# Schematic.net
KiCad netlist of a schematic drawn in Altium Designer
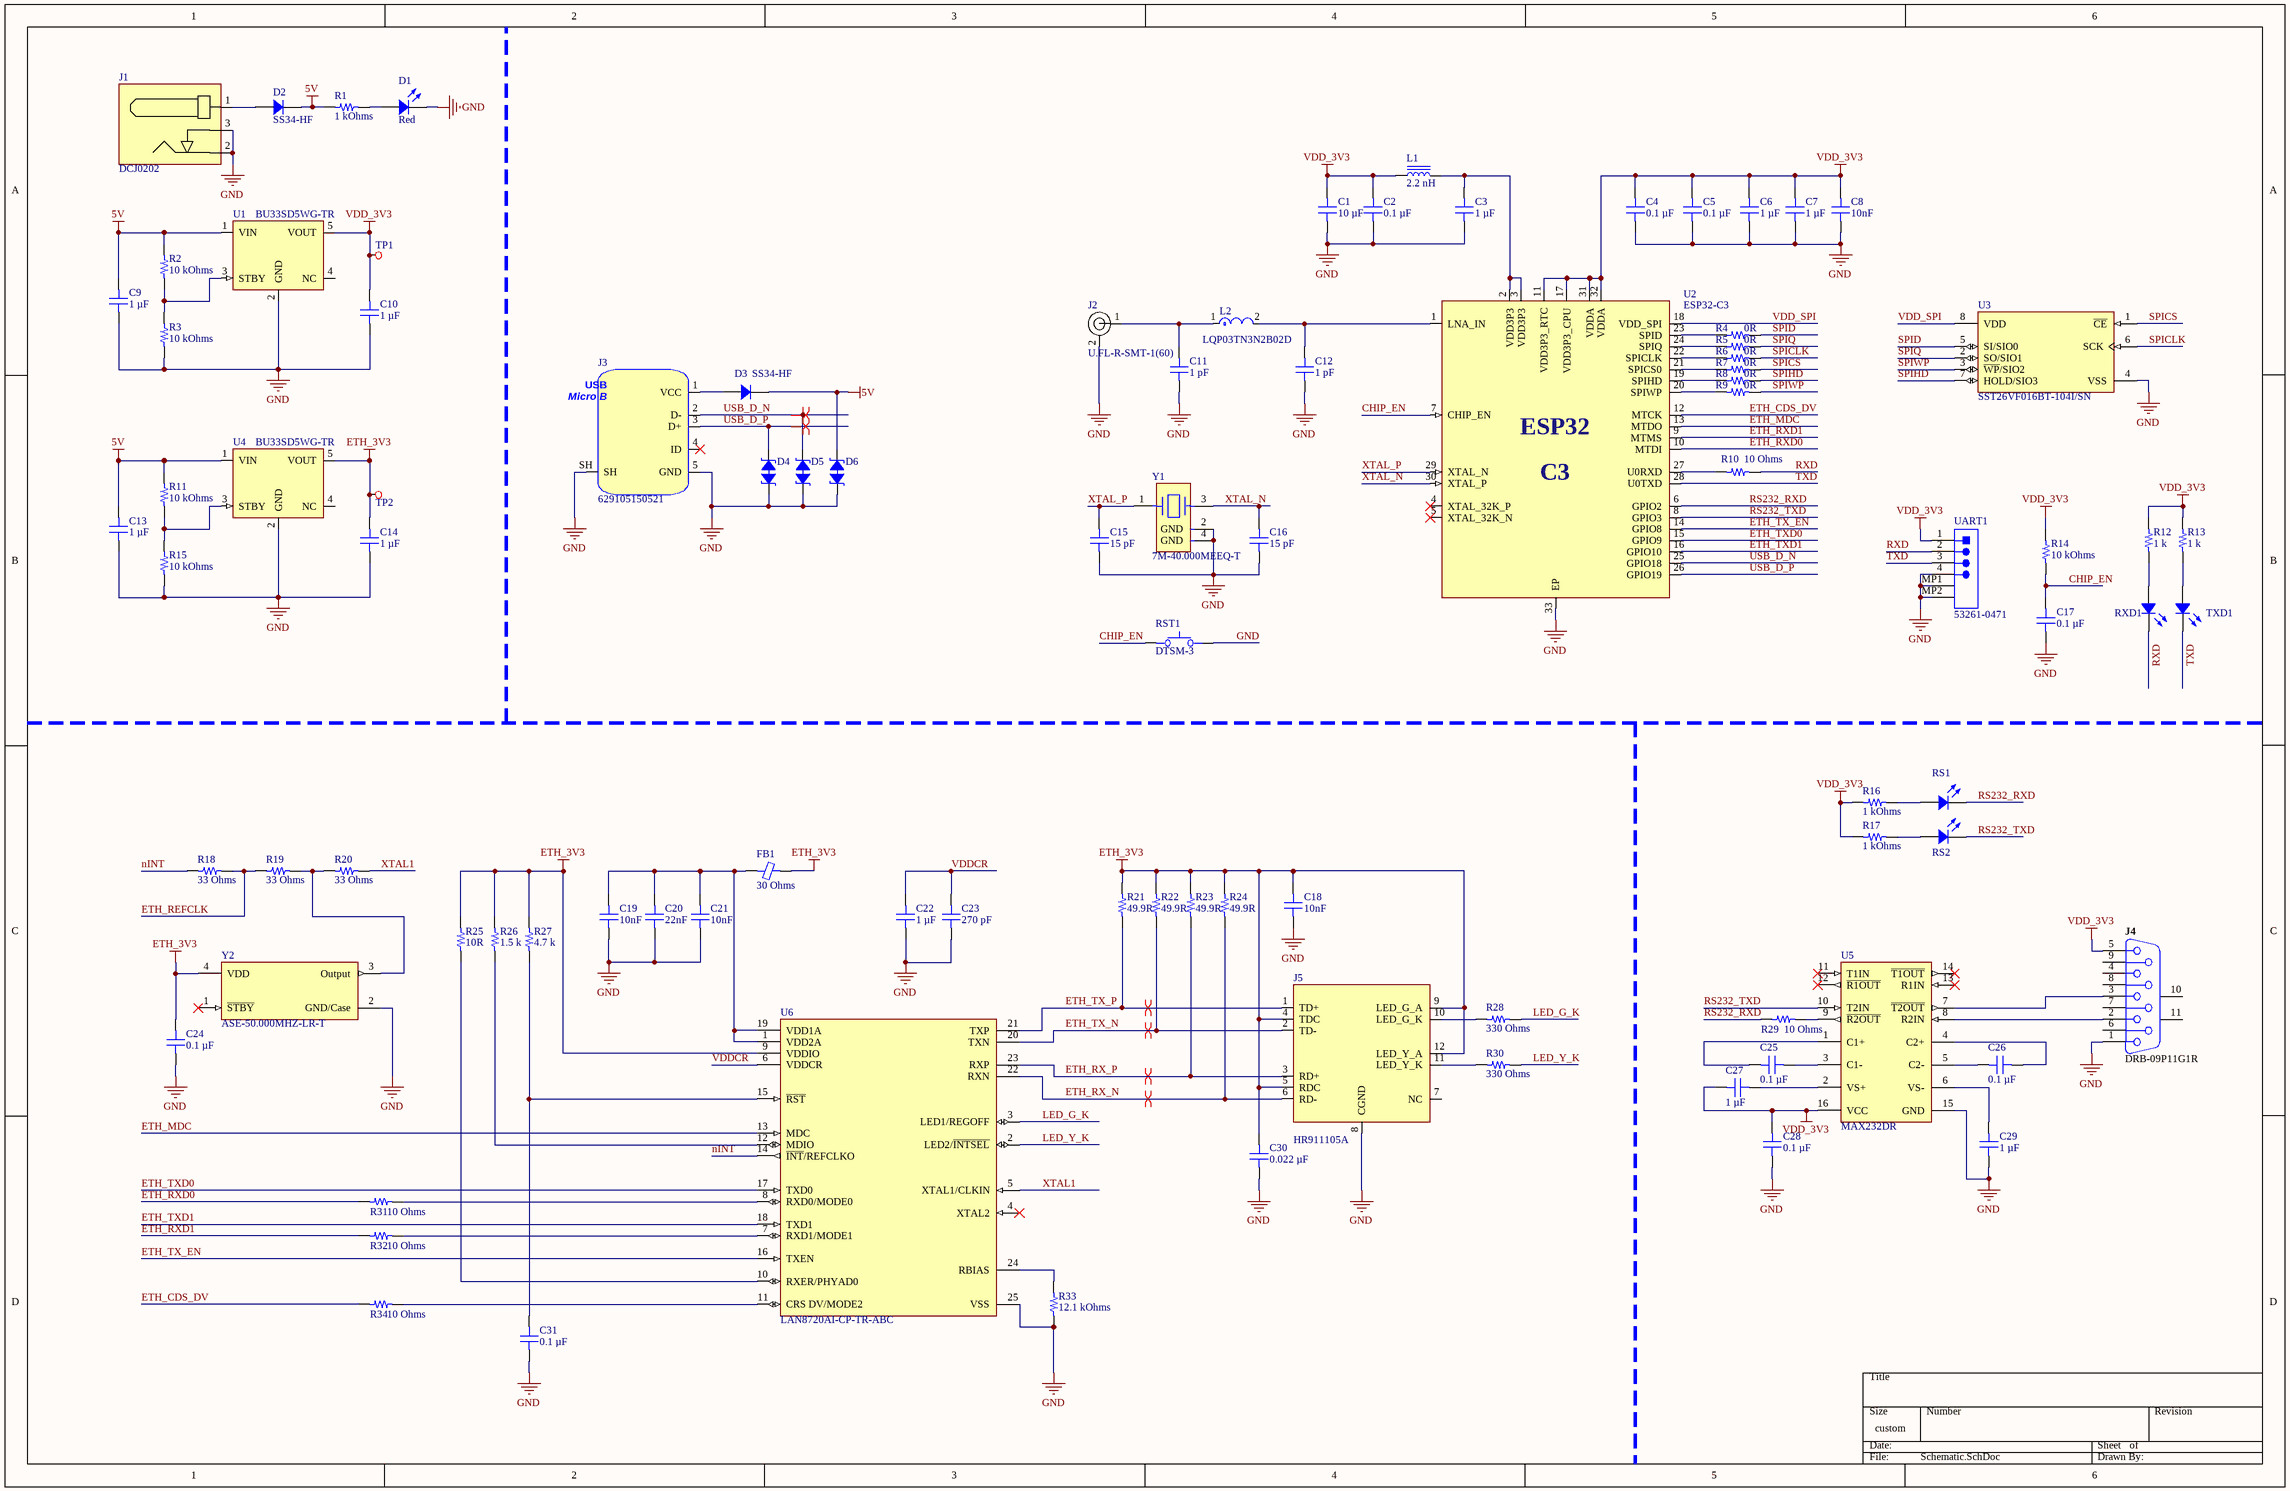
[diagram p0: Schematic.SchDoc]

(export (version "E")
  (design (tool "Eeschema 10.0.6"))
  (components
    (comp (ref "C1")
      (value "10 µF")
      (footprint "CAP 0402_1005")
      (description "CAP CER 10UF 10V X5R 0402")
      (fields
        (field (name "PART NUMBER") "CL05A106MP5NUNC")
        (field (name "CAPACITANCE") "10 µF")
        (field (name "MANUFACTURER") "Samsung Electro-Mechanics")
      )
      (libsource (lib "Celestial Altium Library - altium_library") (part "Capacitor"))
    )
    (comp (ref "C2")
      (value "0.1 µF")
      (footprint "CAP 0402_1005")
      (description "CAP CER 0.1UF 6.3V X5R 0402")
      (fields
        (field (name "PART NUMBER") "CC0402MRX5R5BB104")
        (field (name "CAPACITANCE") "0.1 µF")
        (field (name "MANUFACTURER") "Yageo")
      )
      (libsource (lib "Celestial Altium Library - altium_library") (part "Capacitor"))
    )
    (comp (ref "C3")
      (value "1 µF")
      (footprint "MURATA GRM155 0402_1005")
      (description "CAP CER 1UF 10V X7S 0402")
      (fields
        (field (name "PART NUMBER") "GRM155C71A105KE11D")
        (field (name "CAPACITANCE") "1 µF")
        (field (name "MANUFACTURER") "Murata Electronics")
      )
      (libsource (lib "Celestial Altium Library - altium_library") (part "Capacitor"))
    )
    (comp (ref "C4")
      (value "0.1 µF")
      (footprint "CAP 0402_1005")
      (description "CAP CER 0.1UF 6.3V X5R 0402")
      (fields
        (field (name "PART NUMBER") "CC0402MRX5R5BB104")
        (field (name "CAPACITANCE") "0.1 µF")
        (field (name "MANUFACTURER") "Yageo")
      )
      (libsource (lib "Celestial Altium Library - altium_library") (part "Capacitor"))
    )
    (comp (ref "C5")
      (value "0.1 µF")
      (footprint "CAP 0402_1005")
      (description "CAP CER 0.1UF 6.3V X5R 0402")
      (fields
        (field (name "PART NUMBER") "CC0402MRX5R5BB104")
        (field (name "CAPACITANCE") "0.1 µF")
        (field (name "MANUFACTURER") "Yageo")
      )
      (libsource (lib "Celestial Altium Library - altium_library") (part "Capacitor"))
    )
    (comp (ref "C6")
      (value "1 µF")
      (footprint "MURATA GRM155 0402_1005")
      (description "CAP CER 1UF 10V X7S 0402")
      (fields
        (field (name "PART NUMBER") "GRM155C71A105KE11D")
        (field (name "CAPACITANCE") "1 µF")
        (field (name "MANUFACTURER") "Murata Electronics")
      )
      (libsource (lib "Celestial Altium Library - altium_library") (part "Capacitor"))
    )
    (comp (ref "C7")
      (value "1 µF")
      (footprint "MURATA GRM155 0402_1005")
      (description "CAP CER 1UF 10V X7S 0402")
      (fields
        (field (name "PART NUMBER") "GRM155C71A105KE11D")
        (field (name "CAPACITANCE") "1 µF")
        (field (name "MANUFACTURER") "Murata Electronics")
      )
      (libsource (lib "Celestial Altium Library - altium_library") (part "Capacitor"))
    )
    (comp (ref "C8")
      (value "10000 pF")
      (footprint "CAP 0402_1005")
      (description "CAP CER 0402 10NF 50V X7R 20%")
      (fields
        (field (name "PART NUMBER") "C0402C103M5RECAUTO")
        (field (name "CAPACITANCE") "10nF")
        (field (name "MANUFACTURER") "KEMET")
      )
      (libsource (lib "Celestial Altium Library - altium_library") (part "Capacitor"))
    )
    (comp (ref "C9")
      (value "1 µF")
      (footprint "MURATA GRM155 0402_1005")
      (description "CAP CER 1UF 10V X7S 0402")
      (fields
        (field (name "PART NUMBER") "GRM155C71A105KE11D")
        (field (name "CAPACITANCE") "1 µF")
        (field (name "MANUFACTURER") "Murata Electronics")
      )
      (libsource (lib "Celestial Altium Library - altium_library") (part "Capacitor"))
    )
    (comp (ref "C10")
      (value "1 µF")
      (footprint "MURATA GRM155 0402_1005")
      (description "CAP CER 1UF 10V X7S 0402")
      (fields
        (field (name "PART NUMBER") "GRM155C71A105KE11D")
        (field (name "CAPACITANCE") "1 µF")
        (field (name "MANUFACTURER") "Murata Electronics")
      )
      (libsource (lib "Celestial Altium Library - altium_library") (part "Capacitor"))
    )
    (comp (ref "C11")
      (value "1 pF")
      (footprint "CAP 0201_0603")
      (description "CAP CER 1PF 50V C0G/NP0 0201")
      (fields
        (field (name "PART NUMBER") "0201N1R0C500CT")
        (field (name "CAPACITANCE") "1 pF")
        (field (name "MANUFACTURER") "Walsin Technology Corporation")
      )
      (libsource (lib "Celestial Altium Library - altium_library") (part "Capacitor"))
    )
    (comp (ref "C12")
      (value "1 pF")
      (footprint "CAP 0201_0603")
      (description "CAP CER 1PF 50V C0G/NP0 0201")
      (fields
        (field (name "PART NUMBER") "0201N1R0C500CT")
        (field (name "CAPACITANCE") "1 pF")
        (field (name "MANUFACTURER") "Walsin Technology Corporation")
      )
      (libsource (lib "Celestial Altium Library - altium_library") (part "Capacitor"))
    )
    (comp (ref "C13")
      (value "1 µF")
      (footprint "MURATA GRM155 0402_1005")
      (description "CAP CER 1UF 10V X7S 0402")
      (fields
        (field (name "PART NUMBER") "GRM155C71A105KE11D")
        (field (name "CAPACITANCE") "1 µF")
        (field (name "MANUFACTURER") "Murata Electronics")
      )
      (libsource (lib "Celestial Altium Library - altium_library") (part "Capacitor"))
    )
    (comp (ref "C14")
      (value "1 µF")
      (footprint "MURATA GRM155 0402_1005")
      (description "CAP CER 1UF 10V X7S 0402")
      (fields
        (field (name "PART NUMBER") "GRM155C71A105KE11D")
        (field (name "CAPACITANCE") "1 µF")
        (field (name "MANUFACTURER") "Murata Electronics")
      )
      (libsource (lib "Celestial Altium Library - altium_library") (part "Capacitor"))
    )
    (comp (ref "C15")
      (value "15 pF")
      (footprint "CAP 0402_1005")
      (description "CAP CER 15PF 50V C0G/NP0 0402")
      (fields
        (field (name "PART NUMBER") "CBR04C150J5GAC")
        (field (name "CAPACITANCE") "15 pF")
        (field (name "MANUFACTURER") "KEMET")
      )
      (libsource (lib "Celestial Altium Library - altium_library") (part "Capacitor"))
    )
    (comp (ref "C16")
      (value "15 pF")
      (footprint "CAP 0402_1005")
      (description "CAP CER 15PF 50V C0G/NP0 0402")
      (fields
        (field (name "PART NUMBER") "CBR04C150J5GAC")
        (field (name "CAPACITANCE") "15 pF")
        (field (name "MANUFACTURER") "KEMET")
      )
      (libsource (lib "Celestial Altium Library - altium_library") (part "Capacitor"))
    )
    (comp (ref "C17")
      (value "0.1 µF")
      (footprint "CAP 0402_1005")
      (description "CAP CER 0.1UF 6.3V X5R 0402")
      (fields
        (field (name "PART NUMBER") "CC0402MRX5R5BB104")
        (field (name "CAPACITANCE") "0.1 µF")
        (field (name "MANUFACTURER") "Yageo")
      )
      (libsource (lib "Celestial Altium Library - altium_library") (part "Capacitor"))
    )
    (comp (ref "C18")
      (value "10000 pF")
      (footprint "CAP 0402_1005")
      (description "CAP CER 0402 10NF 50V X7R 20%")
      (fields
        (field (name "PART NUMBER") "C0402C103M5RECAUTO")
        (field (name "CAPACITANCE") "10nF")
        (field (name "MANUFACTURER") "KEMET")
      )
      (libsource (lib "Celestial Altium Library - altium_library") (part "Capacitor"))
    )
    (comp (ref "C19")
      (value "10000 pF")
      (footprint "CAP 0402_1005")
      (description "CAP CER 0402 10NF 50V X7R 20%")
      (fields
        (field (name "PART NUMBER") "C0402C103M5RECAUTO")
        (field (name "CAPACITANCE") "10nF")
        (field (name "MANUFACTURER") "KEMET")
      )
      (libsource (lib "Celestial Altium Library - altium_library") (part "Capacitor"))
    )
    (comp (ref "C20")
      (value "0.022 µF")
      (footprint "CAP 0402_1005")
      (description "CAP CER 0402 22NF 50V X7R 10%")
      (fields
        (field (name "PART NUMBER") "C0402C223K5RECAUTO")
        (field (name "CAPACITANCE") "22nF")
        (field (name "MANUFACTURER") "KEMET")
      )
      (libsource (lib "Celestial Altium Library - altium_library") (part "Capacitor"))
    )
    (comp (ref "C21")
      (value "10000 pF")
      (footprint "CAP 0402_1005")
      (description "CAP CER 0402 10NF 50V X7R 20%")
      (fields
        (field (name "PART NUMBER") "C0402C103M5RECAUTO")
        (field (name "CAPACITANCE") "10nF")
        (field (name "MANUFACTURER") "KEMET")
      )
      (libsource (lib "Celestial Altium Library - altium_library") (part "Capacitor"))
    )
    (comp (ref "C22")
      (value "1 µF")
      (footprint "MURATA GRM155 0402_1005")
      (description "CAP CER 1UF 10V X7S 0402")
      (fields
        (field (name "PART NUMBER") "GRM155C71A105KE11D")
        (field (name "CAPACITANCE") "1 µF")
        (field (name "MANUFACTURER") "Murata Electronics")
      )
      (libsource (lib "Celestial Altium Library - altium_library") (part "Capacitor"))
    )
    (comp (ref "C23")
      (value "270 pF")
      (footprint "CAP 0402_1005")
      (description "CAP CER 270PF 50V C0G/NP0 0402")
      (fields
        (field (name "PART NUMBER") "C0402C271J5GAC7867")
        (field (name "CAPACITANCE") "270 pF")
        (field (name "MANUFACTURER") "KEMET")
      )
      (libsource (lib "Celestial Altium Library - altium_library") (part "Capacitor"))
    )
    (comp (ref "C24")
      (value "0.1 µF")
      (footprint "CAP 0402_1005")
      (description "CAP CER 0.1UF 6.3V X5R 0402")
      (fields
        (field (name "PART NUMBER") "CC0402MRX5R5BB104")
        (field (name "CAPACITANCE") "0.1 µF")
        (field (name "MANUFACTURER") "Yageo")
      )
      (libsource (lib "Celestial Altium Library - altium_library") (part "Capacitor"))
    )
    (comp (ref "C25")
      (value "0.1 µF")
      (footprint "CAP 0402_1005")
      (description "CAP CER 0.1UF 6.3V X5R 0402")
      (fields
        (field (name "PART NUMBER") "CC0402MRX5R5BB104")
        (field (name "CAPACITANCE") "0.1 µF")
        (field (name "MANUFACTURER") "Yageo")
      )
      (libsource (lib "Celestial Altium Library - altium_library") (part "Capacitor"))
    )
    (comp (ref "C26")
      (value "0.1 µF")
      (footprint "CAP 0402_1005")
      (description "CAP CER 0.1UF 6.3V X5R 0402")
      (fields
        (field (name "PART NUMBER") "CC0402MRX5R5BB104")
        (field (name "CAPACITANCE") "0.1 µF")
        (field (name "MANUFACTURER") "Yageo")
      )
      (libsource (lib "Celestial Altium Library - altium_library") (part "Capacitor"))
    )
    (comp (ref "C27")
      (value "1 µF")
      (footprint "MURATA GRM155 0402_1005")
      (description "CAP CER 1UF 10V X7S 0402")
      (fields
        (field (name "PART NUMBER") "GRM155C71A105KE11D")
        (field (name "CAPACITANCE") "1 µF")
        (field (name "MANUFACTURER") "Murata Electronics")
      )
      (libsource (lib "Celestial Altium Library - altium_library") (part "Capacitor"))
    )
    (comp (ref "C28")
      (value "0.1 µF")
      (footprint "CAP 0402_1005")
      (description "CAP CER 0.1UF 6.3V X5R 0402")
      (fields
        (field (name "PART NUMBER") "CC0402MRX5R5BB104")
        (field (name "CAPACITANCE") "0.1 µF")
        (field (name "MANUFACTURER") "Yageo")
      )
      (libsource (lib "Celestial Altium Library - altium_library") (part "Capacitor"))
    )
    (comp (ref "C29")
      (value "1 µF")
      (footprint "MURATA GRM155 0402_1005")
      (description "CAP CER 1UF 10V X7S 0402")
      (fields
        (field (name "PART NUMBER") "GRM155C71A105KE11D")
        (field (name "CAPACITANCE") "1 µF")
        (field (name "MANUFACTURER") "Murata Electronics")
      )
      (libsource (lib "Celestial Altium Library - altium_library") (part "Capacitor"))
    )
    (comp (ref "C30")
      (value "0.022 µF")
      (footprint "CAP 0402_1005")
      (description "CAP CER 0.022UF 50V X7R 0402")
      (fields
        (field (name "PART NUMBER") "0402BB223K500NGT")
        (field (name "CAPACITANCE") "0.022 µF")
        (field (name "MANUFACTURER") "Knowles Novacap")
      )
      (libsource (lib "Celestial Altium Library - altium_library") (part "Capacitor"))
    )
    (comp (ref "C31")
      (value "0.1 µF")
      (footprint "CAP 0402_1005")
      (description "CAP CER 0.1UF 6.3V X5R 0402")
      (fields
        (field (name "PART NUMBER") "CC0402MRX5R5BB104")
        (field (name "CAPACITANCE") "0.1 µF")
        (field (name "MANUFACTURER") "Yageo")
      )
      (libsource (lib "Celestial Altium Library - altium_library") (part "Capacitor"))
    )
    (comp (ref "D1")
      (value "Red")
      (footprint "LED 0603_1608 RED")
      (description "LED RED 0603 SMD")
      (fields (field (name "PART NUMBER") "HSMC-C020") (field (name "MANUFACTURER") "Broadcom Limited"))
      (libsource (lib "Celestial Altium Library - altium_library") (part "LED"))
    )
    (comp (ref "D2")
      (value "SS34-HF")
      (footprint "DO214AC SMA")
      (description "DIODE SCHOTTKY 40V 3A DO214AC")
      (fields (field (name "MANUFACTURER") "Comchip Technology"))
      (libsource (lib "Celestial Altium Library - altium_library") (part "Diode"))
    )
    (comp (ref "D3")
      (value "SS34-HF")
      (footprint "DO214AC SMA")
      (description "DIODE SCHOTTKY 40V 3A DO214AC")
      (fields (field (name "MANUFACTURER") "Comchip Technology"))
      (libsource (lib "Celestial Altium Library - altium_library") (part "Diode"))
    )
    (comp (ref "D4")
      (value "SD05C-TP")
      (footprint "MCC SOD-323")
      (description "5V,ESD PROTECTION DEVICES,SOD-32")
      (fields (field (name "MANUFACTURER") "Micro Commercial Co"))
      (libsource (lib "Celestial Altium Library - altium_library") (part "MCC SOD323 BIDIR TVS"))
    )
    (comp (ref "D5")
      (value "SD05C-TP")
      (footprint "MCC SOD-323")
      (description "5V,ESD PROTECTION DEVICES,SOD-32")
      (fields (field (name "MANUFACTURER") "Micro Commercial Co"))
      (libsource (lib "Celestial Altium Library - altium_library") (part "MCC SOD323 BIDIR TVS"))
    )
    (comp (ref "D6")
      (value "SD05C-TP")
      (footprint "MCC SOD-323")
      (description "5V,ESD PROTECTION DEVICES,SOD-32")
      (fields (field (name "MANUFACTURER") "Micro Commercial Co"))
      (libsource (lib "Celestial Altium Library - altium_library") (part "MCC SOD323 BIDIR TVS"))
    )
    (comp (ref "FB1")
      (value "30 Ohms")
      (footprint "FER 0402_1005")
      (description "FERRITE BEAD 30 OHM 0402 1LN")
      (fields
        (field (name "PART NUMBER") "BLM15KD300SN1D")
        (field (name "MANUFACTURER") "Murata Electronics")
      )
      (libsource (lib "Celestial Altium Library - altium_library") (part "Ferrite Chip"))
    )
    (comp (ref "J1")
      (value "DCJ0202")
      (footprint "DCJ0202")
      (description "DC Barrell Jack 2.1mm 24V 5A THT")
      (fields (field (name "MANUFACTURER") "CONEC"))
      (libsource (lib "PhilsLab Lib") (part "DCJ0202"))
    )
    (comp (ref "J2")
      (value "U.FL-R-SMT-1(60)")
      (footprint "U.FL-R-SMT-1(60)")
      (description "RF Connector u.FL 50 Ohms 6 GHz")
      (fields (field (name "MANUFACTURER") "Hirose Connector"))
      (libsource (lib "PhilsLab Lib") (part "U.FL-R-SMT-1(60)"))
    )
    (comp (ref "J3")
      (value "629105150521")
      (footprint "629105150521")
      (description "USB Connector Type Micro B 2.0 SMD")
      (fields (field (name "MANUFACTURER") "Wurth"))
      (libsource (lib "PhilsLab Lib") (part "629105150521"))
    )
    (comp (ref "J4")
      (value "DRB-09P11G1R")
      (footprint "DB9_MALE")
      (description "Connector, DB9 R/A Through-hole Male")
      (libsource (lib "TechMT.VN_Lib_Project v2") (part "CON 9 Male"))
    )
    (comp (ref "J5")
      (value "HR911105A")
      (footprint "HR911105A")
      (description "Single Port RJ45 Connector w/ Integrated Magnetic and LED 10/100 Base-T")
      (fields (field (name "MANUFACTURER") "HanRun"))
      (libsource (lib "PhilsLab Lib") (part "HR911105A"))
    )
    (comp (ref "L1")
      (value "2.2 nH")
      (footprint "IND 0402_1005")
      (description "FIXED IND 2.2NH 960MA 70MOHM SMD")
      (fields
        (field (name "PART NUMBER") "0402HS-2N2EJTS")
        (field (name "MANUFACTURER") "Delta Electronics/Components")
      )
      (libsource (lib "Celestial Altium Library - altium_library") (part "Inductor"))
    )
    (comp (ref "L2")
      (value "LQP03TN3N2B02D")
      (footprint "FP-LQP03TG_02-IPC_B")
      (description "Film type RF Inductor 3.2nH ±0.1nH 450mA 0.25Ω 0201 (0603)")
      (libsource (lib "Altium Content Vault") (part "4cc4b267dca4c8e51f7102f422741d8"))
    )
    (comp (ref "R1")
      (value "1 kOhms")
      (footprint "YAGEO RES 0402_1005")
      (description "RES SMD 1K OHM 0.1% 1/16W 0402")
      (fields (field (name "PART NUMBER") "AT0402BRD071KL") (field (name "MANUFACTURER") "Yageo"))
      (libsource (lib "Celestial Altium Library - altium_library") (part "Resistor"))
    )
    (comp (ref "R2")
      (value "10 kOhms")
      (footprint "RES 0603_1608")
      (description "RES 10K OHM 0.1% 1/16W 0603")
      (fields
        (field (name "PART NUMBER") "RNCS0603BKE10K0")
        (field (name "MANUFACTURER") "Stackpole Electronics Inc")
      )
      (libsource (lib "Celestial Altium Library - altium_library") (part "Resistor"))
    )
    (comp (ref "R3")
      (value "10 kOhms")
      (footprint "RES 0603_1608")
      (description "RES 10K OHM 0.1% 1/16W 0603")
      (fields
        (field (name "PART NUMBER") "RNCS0603BKE10K0")
        (field (name "MANUFACTURER") "Stackpole Electronics Inc")
      )
      (libsource (lib "Celestial Altium Library - altium_library") (part "Resistor"))
    )
    (comp (ref "R4")
      (value "0R")
      (footprint "RES 0402_1005")
      (description "RES SMD 0 OHM JUMPER 1/5W 0402")
      (fields (field (name "PART NUMBER") "CRCW04020000Z0EDHP") (field (name "MANUFACTURER") "Vishay Dale"))
      (libsource (lib "Celestial Altium Library - altium_library") (part "Resistor"))
    )
    (comp (ref "R5")
      (value "0R")
      (footprint "RES 0402_1005")
      (description "RES SMD 0 OHM JUMPER 1/5W 0402")
      (fields (field (name "PART NUMBER") "CRCW04020000Z0EDHP") (field (name "MANUFACTURER") "Vishay Dale"))
      (libsource (lib "Celestial Altium Library - altium_library") (part "Resistor"))
    )
    (comp (ref "R6")
      (value "0R")
      (footprint "RES 0402_1005")
      (description "RES SMD 0 OHM JUMPER 1/5W 0402")
      (fields (field (name "PART NUMBER") "CRCW04020000Z0EDHP") (field (name "MANUFACTURER") "Vishay Dale"))
      (libsource (lib "Celestial Altium Library - altium_library") (part "Resistor"))
    )
    (comp (ref "R7")
      (value "0R")
      (footprint "RES 0402_1005")
      (description "RES SMD 0 OHM JUMPER 1/5W 0402")
      (fields (field (name "PART NUMBER") "CRCW04020000Z0EDHP") (field (name "MANUFACTURER") "Vishay Dale"))
      (libsource (lib "Celestial Altium Library - altium_library") (part "Resistor"))
    )
    (comp (ref "R8")
      (value "0R")
      (footprint "RES 0402_1005")
      (description "RES SMD 0 OHM JUMPER 1/5W 0402")
      (fields (field (name "PART NUMBER") "CRCW04020000Z0EDHP") (field (name "MANUFACTURER") "Vishay Dale"))
      (libsource (lib "Celestial Altium Library - altium_library") (part "Resistor"))
    )
    (comp (ref "R9")
      (value "0R")
      (footprint "RES 0402_1005")
      (description "RES SMD 0 OHM JUMPER 1/5W 0402")
      (fields (field (name "PART NUMBER") "CRCW04020000Z0EDHP") (field (name "MANUFACTURER") "Vishay Dale"))
      (libsource (lib "Celestial Altium Library - altium_library") (part "Resistor"))
    )
    (comp (ref "R10")
      (value "10 Ohms")
      (footprint "RES 0402_1005")
      (description "RES SMD 10 OHM 0.5% 1/16W 0402")
      (fields (field (name "PART NUMBER") "RR0510R-100-D") (field (name "MANUFACTURER") "Susumu"))
      (libsource (lib "Celestial Altium Library - altium_library") (part "Resistor"))
    )
    (comp (ref "R11")
      (value "10 kOhms")
      (footprint "RES 0603_1608")
      (description "RES 10K OHM 0.1% 1/16W 0603")
      (fields
        (field (name "PART NUMBER") "RNCS0603BKE10K0")
        (field (name "MANUFACTURER") "Stackpole Electronics Inc")
      )
      (libsource (lib "Celestial Altium Library - altium_library") (part "Resistor"))
    )
    (comp (ref "R12")
      (value "1 k")
      (footprint "RES 0402_1005")
      (description "RES 1 KOHMS 0.1% 1/16W 0402")
      (fields
        (field (name "PART NUMBER") "RQ73C1E1K0BTD")
        (field (name "MANUFACTURER") "TE Connectivity Passive Product")
      )
      (libsource (lib "Celestial Altium Library - altium_library") (part "Resistor"))
    )
    (comp (ref "R13")
      (value "1 k")
      (footprint "RES 0402_1005")
      (description "RES 1 KOHMS 0.1% 1/16W 0402")
      (fields
        (field (name "PART NUMBER") "RQ73C1E1K0BTD")
        (field (name "MANUFACTURER") "TE Connectivity Passive Product")
      )
      (libsource (lib "Celestial Altium Library - altium_library") (part "Resistor"))
    )
    (comp (ref "R14")
      (value "10 kOhms")
      (footprint "RES 0402_1005")
      (description "RES 10K OHM 0.1% 1/10W 0402")
      (fields
        (field (name "PART NUMBER") "RP73PF1E10KBTD")
        (field (name "MANUFACTURER") "TE Connectivity Passive Product")
      )
      (libsource (lib "Celestial Altium Library - altium_library") (part "Resistor"))
    )
    (comp (ref "R15")
      (value "10 kOhms")
      (footprint "RES 0603_1608")
      (description "RES 10K OHM 0.1% 1/16W 0603")
      (fields
        (field (name "PART NUMBER") "RNCS0603BKE10K0")
        (field (name "MANUFACTURER") "Stackpole Electronics Inc")
      )
      (libsource (lib "Celestial Altium Library - altium_library") (part "Resistor"))
    )
    (comp (ref "R16")
      (value "1 kOhms")
      (footprint "RES 0402_1005")
      (description "RES 1 KOHMS 0.1% 1/16W 0402")
      (fields
        (field (name "PART NUMBER") "RQ73C1E1K0BTD")
        (field (name "MANUFACTURER") "TE Connectivity Passive Product")
      )
      (libsource (lib "Celestial Altium Library - altium_library") (part "Resistor"))
    )
    (comp (ref "R17")
      (value "1 kOhms")
      (footprint "RES 0402_1005")
      (description "RES 1 KOHMS 0.1% 1/16W 0402")
      (fields
        (field (name "PART NUMBER") "RQ73C1E1K0BTD")
        (field (name "MANUFACTURER") "TE Connectivity Passive Product")
      )
      (libsource (lib "Celestial Altium Library - altium_library") (part "Resistor"))
    )
    (comp (ref "R18")
      (value "33 Ohms")
      (footprint "RES 0402_1005")
      (description "RES SMD 33 OHM 0.1% 1/16W 0402")
      (fields
        (field (name "PART NUMBER") "CPF0402B33RE")
        (field (name "MANUFACTURER") "TE Connectivity Passive Product")
      )
      (libsource (lib "Celestial Altium Library - altium_library") (part "Resistor"))
    )
    (comp (ref "R19")
      (value "33 Ohms")
      (footprint "RES 0402_1005")
      (description "RES SMD 33 OHM 0.1% 1/16W 0402")
      (fields
        (field (name "PART NUMBER") "CPF0402B33RE")
        (field (name "MANUFACTURER") "TE Connectivity Passive Product")
      )
      (libsource (lib "Celestial Altium Library - altium_library") (part "Resistor"))
    )
    (comp (ref "R20")
      (value "33 Ohms")
      (footprint "RES 0402_1005")
      (description "RES SMD 33 OHM 0.1% 1/16W 0402")
      (fields
        (field (name "PART NUMBER") "CPF0402B33RE")
        (field (name "MANUFACTURER") "TE Connectivity Passive Product")
      )
      (libsource (lib "Celestial Altium Library - altium_library") (part "Resistor"))
    )
    (comp (ref "R21")
      (value "49.9R")
      (footprint "RES 0402_1005")
      (description "RES 49.9 OHM 1% 1/16W 0402")
      (fields (field (name "PART NUMBER") "SFR01MZPF49R9") (field (name "MANUFACTURER") "Rohm Semiconductor"))
      (libsource (lib "Celestial Altium Library - altium_library") (part "Resistor"))
    )
    (comp (ref "R22")
      (value "49.9R")
      (footprint "RES 0402_1005")
      (description "RES 49.9 OHM 1% 1/16W 0402")
      (fields (field (name "PART NUMBER") "SFR01MZPF49R9") (field (name "MANUFACTURER") "Rohm Semiconductor"))
      (libsource (lib "Celestial Altium Library - altium_library") (part "Resistor"))
    )
    (comp (ref "R23")
      (value "49.9R")
      (footprint "RES 0402_1005")
      (description "RES 49.9 OHM 1% 1/16W 0402")
      (fields (field (name "PART NUMBER") "SFR01MZPF49R9") (field (name "MANUFACTURER") "Rohm Semiconductor"))
      (libsource (lib "Celestial Altium Library - altium_library") (part "Resistor"))
    )
    (comp (ref "R24")
      (value "49.9R")
      (footprint "RES 0402_1005")
      (description "RES 49.9 OHM 1% 1/16W 0402")
      (fields (field (name "PART NUMBER") "SFR01MZPF49R9") (field (name "MANUFACTURER") "Rohm Semiconductor"))
      (libsource (lib "Celestial Altium Library - altium_library") (part "Resistor"))
    )
    (comp (ref "R25")
      (value "10R")
      (footprint "RES 0402_1005")
      (description "RES SMD 10 OHM 0.5% 1/16W 0402")
      (fields (field (name "PART NUMBER") "RR0510R-100-D") (field (name "MANUFACTURER") "Susumu"))
      (libsource (lib "Celestial Altium Library - altium_library") (part "Resistor"))
    )
    (comp (ref "R26")
      (value "1.5 k")
      (footprint "RES 0402_1005")
      (description "RES SMD 1.5K OHM 0.5% 1/16W 0402")
      (fields (field (name "PART NUMBER") "RR0510P-152-D") (field (name "MANUFACTURER") "Susumu"))
      (libsource (lib "Celestial Altium Library - altium_library") (part "Resistor"))
    )
    (comp (ref "R27")
      (value "4.7 k")
      (footprint "YAGEO RES 0402_1005")
      (description "RES SMD 4.7K OHM 1% 1/16W 0402")
      (fields (field (name "PART NUMBER") "RT0402FRE074K7L") (field (name "MANUFACTURER") "Yageo"))
      (libsource (lib "Celestial Altium Library - altium_library") (part "Resistor"))
    )
    (comp (ref "R28")
      (value "330 Ohms")
      (footprint "RES 0402_1005")
      (description "RES SMD 330 OHM 0.1% 1/16W 0402")
      (fields
        (field (name "PART NUMBER") "CPF0402B330RE1")
        (field (name "MANUFACTURER") "TE Connectivity Passive Product")
      )
      (libsource (lib "Celestial Altium Library - altium_library") (part "Resistor"))
    )
    (comp (ref "R29")
      (value "10 Ohms")
      (footprint "RES 0402_1005")
      (description "RES SMD 10 OHM 0.5% 1/16W 0402")
      (fields (field (name "PART NUMBER") "RR0510R-100-D") (field (name "MANUFACTURER") "Susumu"))
      (libsource (lib "Celestial Altium Library - altium_library") (part "Resistor"))
    )
    (comp (ref "R30")
      (value "330 Ohms")
      (footprint "RES 0402_1005")
      (description "RES SMD 330 OHM 0.1% 1/16W 0402")
      (fields
        (field (name "PART NUMBER") "CPF0402B330RE1")
        (field (name "MANUFACTURER") "TE Connectivity Passive Product")
      )
      (libsource (lib "Celestial Altium Library - altium_library") (part "Resistor"))
    )
    (comp (ref "R31")
      (value "10 Ohms")
      (footprint "RES 0402_1005")
      (description "RES SMD 10 OHM 0.5% 1/16W 0402")
      (fields (field (name "PART NUMBER") "RR0510R-100-D") (field (name "MANUFACTURER") "Susumu"))
      (libsource (lib "Celestial Altium Library - altium_library") (part "Resistor"))
    )
    (comp (ref "R32")
      (value "10 Ohms")
      (footprint "RES 0402_1005")
      (description "RES SMD 10 OHM 0.5% 1/16W 0402")
      (fields (field (name "PART NUMBER") "RR0510R-100-D") (field (name "MANUFACTURER") "Susumu"))
      (libsource (lib "Celestial Altium Library - altium_library") (part "Resistor"))
    )
    (comp (ref "R33")
      (value "12.1 kOhms")
      (footprint "RES 0402_1005")
      (description "RES SMD 12.1K OHM 1% 1/10W 0402")
      (fields
        (field (name "PART NUMBER") "ERJ-2RKF1212X")
        (field (name "MANUFACTURER") "Panasonic Electronic Components")
      )
      (libsource (lib "Celestial Altium Library - altium_library") (part "Resistor"))
    )
    (comp (ref "R34")
      (value "10 Ohms")
      (footprint "RES 0402_1005")
      (description "RES SMD 10 OHM 0.5% 1/16W 0402")
      (fields (field (name "PART NUMBER") "RR0510R-100-D") (field (name "MANUFACTURER") "Susumu"))
      (libsource (lib "Celestial Altium Library - altium_library") (part "Resistor"))
    )
    (comp (ref "RS1")
      (value "Green")
      (footprint "LED 0603_1608 GREEN")
      (description "LED GREEN 0603 SMD")
      (fields (field (name "PART NUMBER") "5973316507F") (field (name "MANUFACTURER") "Dialight"))
      (libsource (lib "Celestial Altium Library - altium_library") (part "LED"))
    )
    (comp (ref "RS2")
      (value "Yellow")
      (footprint "LED 0603_1608 YELLOW")
      (description "LED YELLOW 0603 SMD")
      (fields (field (name "PART NUMBER") "5990040007F") (field (name "MANUFACTURER") "Dialight"))
      (libsource (lib "Celestial Altium Library - altium_library") (part "LED"))
    )
    (comp (ref "RST1")
      (value "DTSM-3")
      (footprint "DTSM-3")
      (description "Tactile Switch SMD SPST")
      (fields (field (name "MANUFACTURER") "Diptronics"))
      (libsource (lib "PhilsLab Lib") (part "DTSM-3"))
    )
    (comp (ref "RXD1")
      (value "Yellow")
      (footprint "LED 0603_1608 YELLOW")
      (description "LED YELLOW 0603 SMD")
      (fields (field (name "PART NUMBER") "5990040007F") (field (name "MANUFACTURER") "Dialight"))
      (libsource (lib "Celestial Altium Library - altium_library") (part "LED"))
    )
    (comp (ref "TP1")
      (value "TEST_POINT_PAD1MM")
      (footprint "ROUND_1MM")
      (libsource (lib "nemLibrary") (part "TEST_POINT_PAD1MM"))
    )
    (comp (ref "TP2")
      (value "TEST_POINT_PAD1MM")
      (footprint "ROUND_1MM")
      (libsource (lib "nemLibrary") (part "TEST_POINT_PAD1MM"))
    )
    (comp (ref "TXD1")
      (value "Green")
      (footprint "LED 0603_1608 GREEN")
      (description "LED GREEN 0603 SMD")
      (fields (field (name "PART NUMBER") "5973316507F") (field (name "MANUFACTURER") "Dialight"))
      (libsource (lib "Celestial Altium Library - altium_library") (part "LED"))
    )
    (comp (ref "U1")
      (value "BU33SD5WG-TR")
      (footprint "SOT-23-5")
      (description "LDO Voltage Regulator 3.3V 500mA")
      (fields (field (name "MANUFACTURER") "ROHM Semiconductor"))
      (libsource (lib "PhilsLab Lib") (part "BU33SD5WG-TR"))
    )
    (comp (ref "U2")
      (value "ESP32-C3")
      (footprint "QFN32-5x5")
      (fields (field (name "MANUFACTURER") "Espressif"))
      (libsource (lib "PhilsLab Lib") (part "ESP32-C3"))
    )
    (comp (ref "U3")
      (value "SST26VF016BT-104I/SN")
      (footprint "FP-C04-057-SN-IPC_B")
      (description "IC FLASH 16M SPI 104MHZ 8SOIC")
      (libsource (lib "Altium Content Vault") (part "5a484b0505e2c9fae89a7cad477121f"))
    )
    (comp (ref "U4")
      (value "BU33SD5WG-TR")
      (footprint "SOT-23-5")
      (description "LDO Voltage Regulator 3.3V 500mA")
      (fields (field (name "MANUFACTURER") "ROHM Semiconductor"))
      (libsource (lib "PhilsLab Lib") (part "BU33SD5WG-TR"))
    )
    (comp (ref "U5")
      (value "MAX232DR")
      (footprint "D0016A_N")
      (description "Dual EIA-232 Driver / Receiver, 0 to 70 degC, 16-Pin SOIC (D), Green (RoHS & no Sb/Br)")
      (libsource (lib "Altium Content Vault") (part "TI-MAX232-SOIC_D-16"))
    )
    (comp (ref "U6")
      (value "LAN8720AI-CP-TR-ABC")
      (footprint "FP-24-S4QFN-4x4B-0_5P-IPC_C")
      (description "IC TRANSCEIVER FULL 2/2 24SQFN")
      (libsource (lib "Altium Content Vault") (part "12669737dabcafa3a3ef7365d8c4504"))
    )
    (comp (ref "UART1")
      (value "53261-0471")
      (footprint "MOLEX-53261-0471_V")
      (description "Male Header, Pitch 1.25 mm, 1 x 4 Position, Height 3.4 mm, -40 to 85 degC, RoHS, Tape and Reel")
      (fields (field (name "MANUFACTURER") "Molex"))
      (libsource (lib "Altium Content Vault") (part "CN-1P-2M-R4_A"))
    )
    (comp (ref "Y1")
      (value "7M-40.000MEEQ-T")
      (footprint "FP-7M-MFG")
      (description "Crystal 40MHz, 10ppm, 10pF, 50Ω")
      (fields (field (name "TOLERANCE") "10ppm"))
      (libsource (lib "Altium Content Vault") (part "41079aabb0e87794b56622915be14ed"))
    )
    (comp (ref "Y2")
      (value "ASE-50.000MHZ-LR-T")
      (footprint "FP-ASE-MFG")
      (description "XTAL Oscillator 50MHz ±25ppm CMOS 3.3V 4-SMD 3.2mm x 2.5mm")
      (libsource (lib "Altium Content Vault") (part "61a724e6190563596ac712fef61ad37"))
    )
  )
  (nets
    (net (code "2") (name "/CHIP_EN") (class "Default")
      (node (ref "C17") (pin "2") (pinfunction "2_2") (pintype "passive"))
      (node (ref "R14") (pin "1") (pinfunction "1_1") (pintype "passive"))
      (node (ref "RST1") (pin "1") (pintype "passive"))
      (node (ref "U2") (pin "7") (pinfunction "CHIP_EN_7") (pintype "input"))
    )
    (net (code "3") (name "/ETH_CDS_DV") (class "Default")
      (node (ref "R34") (pin "1") (pinfunction "1_1") (pintype "passive"))
      (node (ref "U2") (pin "12") (pinfunction "MTCK_12") (pintype "bidirectional"))
    )
    (net (code "4") (name "/ETH_MDC") (class "Default")
      (node (ref "U2") (pin "13") (pinfunction "MTDO_13") (pintype "bidirectional"))
      (node (ref "U6") (pin "13") (pinfunction "MDC_13") (pintype "input"))
    )
    (net (code "5") (name "/ETH_REFCLK") (class "Default")
      (node (ref "R18") (pin "2") (pinfunction "2_2") (pintype "passive"))
      (node (ref "R19") (pin "1") (pinfunction "1_1") (pintype "passive"))
    )
    (net (code "6") (name "/ETH_RXD0") (class "Default")
      (node (ref "R31") (pin "1") (pinfunction "1_1") (pintype "passive"))
      (node (ref "U2") (pin "10") (pinfunction "MTDI_10") (pintype "bidirectional"))
    )
    (net (code "7") (name "/ETH_RXD1") (class "Default")
      (node (ref "R32") (pin "1") (pinfunction "1_1") (pintype "passive"))
      (node (ref "U2") (pin "9") (pinfunction "MTMS_9") (pintype "bidirectional"))
    )
    (net (code "8") (name "/ETH_RX_N") (class "Default")
      (node (ref "J5") (pin "6") (pinfunction "RD-_6") (pintype "passive"))
      (node (ref "R24") (pin "1") (pinfunction "1_1") (pintype "passive"))
      (node (ref "U6") (pin "22") (pinfunction "RXN_22") (pintype "passive"))
    )
    (net (code "9") (name "/ETH_RX_P") (class "Default")
      (node (ref "J5") (pin "3") (pinfunction "RD+_3") (pintype "passive"))
      (node (ref "R23") (pin "1") (pinfunction "1_1") (pintype "passive"))
      (node (ref "U6") (pin "23") (pinfunction "RXP_23") (pintype "passive"))
    )
    (net (code "10") (name "/ETH_TXD0") (class "Default")
      (node (ref "U2") (pin "15") (pinfunction "GPIO9_15") (pintype "bidirectional"))
      (node (ref "U6") (pin "17") (pinfunction "TXD0_17") (pintype "input"))
    )
    (net (code "11") (name "/ETH_TXD1") (class "Default")
      (node (ref "U2") (pin "16") (pinfunction "GPIO10_16") (pintype "bidirectional"))
      (node (ref "U6") (pin "18") (pinfunction "TXD1_18") (pintype "input"))
    )
    (net (code "12") (name "/ETH_TX_EN") (class "Default")
      (node (ref "U2") (pin "14") (pinfunction "GPIO8_14") (pintype "bidirectional"))
      (node (ref "U6") (pin "16") (pinfunction "TXEN_16") (pintype "input"))
    )
    (net (code "13") (name "/ETH_TX_N") (class "Default")
      (node (ref "J5") (pin "2") (pinfunction "TD-_2") (pintype "passive"))
      (node (ref "R22") (pin "1") (pinfunction "1_1") (pintype "passive"))
      (node (ref "U6") (pin "20") (pinfunction "TXN_20") (pintype "passive"))
    )
    (net (code "14") (name "/ETH_TX_P") (class "Default")
      (node (ref "J5") (pin "1") (pinfunction "TD+_1") (pintype "passive"))
      (node (ref "R21") (pin "1") (pinfunction "1_1") (pintype "passive"))
      (node (ref "U6") (pin "21") (pinfunction "TXP_21") (pintype "passive"))
    )
    (net (code "15") (name "/LED_G_K") (class "Default")
      (node (ref "R28") (pin "2") (pinfunction "2_2") (pintype "passive"))
      (node (ref "U6") (pin "3") (pinfunction "LED1/REGOFF_3") (pintype "bidirectional"))
    )
    (net (code "16") (name "/LED_Y_K") (class "Default")
      (node (ref "R30") (pin "2") (pinfunction "2_2") (pintype "passive"))
      (node (ref "U6") (pin "2") (pinfunction "LED2/~{INTSEL}_2") (pintype "bidirectional"))
    )
    (net (code "17") (name "/RS232_RXD") (class "Default")
      (node (ref "R29") (pin "1") (pinfunction "1_1") (pintype "passive"))
      (node (ref "RS1") (pin "2") (pinfunction "2_2") (pintype "passive"))
      (node (ref "U2") (pin "6") (pinfunction "GPIO2_6") (pintype "bidirectional"))
    )
    (net (code "18") (name "/RS232_TXD") (class "Default")
      (node (ref "RS2") (pin "2") (pinfunction "2_2") (pintype "passive"))
      (node (ref "U2") (pin "8") (pinfunction "GPIO3_8") (pintype "bidirectional"))
      (node (ref "U5") (pin "10") (pinfunction "T2IN_10") (pintype "input"))
    )
    (net (code "19") (name "/RXD") (class "Default")
      (node (ref "R10") (pin "2") (pinfunction "2_2") (pintype "passive"))
      (node (ref "RXD1") (pin "2") (pinfunction "2_2") (pintype "passive"))
      (node (ref "UART1") (pin "2") (pinfunction "2_2") (pintype "passive"))
    )
    (net (code "20") (name "/SPICLK") (class "Default")
      (node (ref "R6") (pin "2") (pinfunction "2_2") (pintype "passive"))
      (node (ref "U3") (pin "6") (pinfunction "SCK_6") (pintype "input"))
    )
    (net (code "21") (name "/SPICS") (class "Default")
      (node (ref "R7") (pin "2") (pinfunction "2_2") (pintype "passive"))
      (node (ref "U3") (pin "1") (pinfunction "~{CE}_1") (pintype "input"))
    )
    (net (code "22") (name "/SPID") (class "Default")
      (node (ref "R4") (pin "2") (pinfunction "2_2") (pintype "passive"))
      (node (ref "U3") (pin "5") (pinfunction "SI/SIO0_5") (pintype "bidirectional"))
    )
    (net (code "23") (name "/SPIHD") (class "Default")
      (node (ref "R8") (pin "2") (pinfunction "2_2") (pintype "passive"))
      (node (ref "U3") (pin "7") (pinfunction "HOLD/SIO3_7") (pintype "bidirectional"))
    )
    (net (code "24") (name "/SPIQ") (class "Default")
      (node (ref "R5") (pin "2") (pinfunction "2_2") (pintype "passive"))
      (node (ref "U3") (pin "2") (pinfunction "SO/SIO1_2") (pintype "bidirectional"))
    )
    (net (code "25") (name "/SPIWP") (class "Default")
      (node (ref "R9") (pin "2") (pinfunction "2_2") (pintype "passive"))
      (node (ref "U3") (pin "3") (pinfunction "~{WP}/SIO2_3") (pintype "bidirectional"))
    )
    (net (code "26") (name "/TXD") (class "Default")
      (node (ref "TXD1") (pin "2") (pinfunction "2_2") (pintype "passive"))
      (node (ref "U2") (pin "28") (pinfunction "U0TXD_28") (pintype "bidirectional"))
      (node (ref "UART1") (pin "3") (pinfunction "3_3") (pintype "passive"))
    )
    (net (code "27") (name "/USB_D_N") (class "Default")
      (node (ref "D5") (pin "2") (pinfunction "2_2") (pintype "passive"))
      (node (ref "J3") (pin "2") (pinfunction "D-_2") (pintype "passive"))
      (node (ref "U2") (pin "25") (pinfunction "GPIO18_25") (pintype "bidirectional"))
    )
    (net (code "28") (name "/USB_D_P") (class "Default")
      (node (ref "D4") (pin "2") (pinfunction "2_2") (pintype "passive"))
      (node (ref "J3") (pin "3") (pinfunction "D+_3") (pintype "passive"))
      (node (ref "U2") (pin "26") (pinfunction "GPIO19_26") (pintype "bidirectional"))
    )
    (net (code "29") (name "/VDDCR") (class "Default")
      (node (ref "C22") (pin "2") (pinfunction "2_2") (pintype "passive"))
      (node (ref "C23") (pin "2") (pinfunction "2_2") (pintype "passive"))
      (node (ref "U6") (pin "6") (pinfunction "VDDCR_6") (pintype "power_in"))
    )
    (net (code "30") (name "/VDD_SPI") (class "Default")
      (node (ref "U2") (pin "18") (pinfunction "VDD_SPI_18") (pintype "power_in"))
      (node (ref "U3") (pin "8") (pinfunction "VDD_8") (pintype "power_in"))
    )
    (net (code "31") (name "/XTAL1") (class "Default")
      (node (ref "R20") (pin "2") (pinfunction "2_2") (pintype "passive"))
      (node (ref "U6") (pin "5") (pinfunction "XTAL1/CLKIN_5") (pintype "input"))
    )
    (net (code "32") (name "/XTAL_N") (class "Default")
      (node (ref "C16") (pin "2") (pinfunction "2_2") (pintype "passive"))
      (node (ref "U2") (pin "30") (pinfunction "XTAL_P_30") (pintype "input"))
      (node (ref "Y1") (pin "3") (pinfunction "3_3") (pintype "passive"))
    )
    (net (code "33") (name "/XTAL_P") (class "Default")
      (node (ref "C15") (pin "2") (pinfunction "2_2") (pintype "passive"))
      (node (ref "U2") (pin "29") (pinfunction "XTAL_N_29") (pintype "input"))
      (node (ref "Y1") (pin "1") (pinfunction "1_1") (pintype "passive"))
    )
    (net (code "34") (name "/nINT") (class "Default")
      (node (ref "R18") (pin "1") (pinfunction "1_1") (pintype "passive"))
      (node (ref "U6") (pin "14") (pinfunction "~{INT}/REFCLKO_14") (pintype "output"))
    )
    (net (code "35") (name "5V") (class "Default")
      (node (ref "C13") (pin "2") (pinfunction "2_2") (pintype "passive"))
      (node (ref "C9") (pin "2") (pinfunction "2_2") (pintype "passive"))
      (node (ref "D2") (pin "2") (pinfunction "2_2") (pintype "passive"))
      (node (ref "D3") (pin "2") (pinfunction "2_2") (pintype "passive"))
      (node (ref "D6") (pin "2") (pinfunction "2_2") (pintype "passive"))
      (node (ref "R1") (pin "1") (pinfunction "1_1") (pintype "passive"))
      (node (ref "R11") (pin "2") (pinfunction "2_2") (pintype "passive"))
      (node (ref "R2") (pin "2") (pinfunction "2_2") (pintype "passive"))
      (node (ref "U1") (pin "1") (pinfunction "VIN_1") (pintype "power_in"))
      (node (ref "U4") (pin "1") (pinfunction "VIN_1") (pintype "power_in"))
    )
    (net (code "36") (name "ETH_3V3") (class "Default")
      (node (ref "C14") (pin "2") (pinfunction "2_2") (pintype "passive"))
      (node (ref "C18") (pin "2") (pinfunction "2_2") (pintype "passive"))
      (node (ref "C24") (pin "2") (pinfunction "2_2") (pintype "passive"))
      (node (ref "C30") (pin "2") (pinfunction "2_2") (pintype "passive"))
      (node (ref "FB1") (pin "2") (pinfunction "2_2") (pintype "passive"))
      (node (ref "J5") (pin "12") (pinfunction "LED_Y_A_12") (pintype "passive"))
      (node (ref "J5") (pin "4") (pinfunction "TDC_4") (pintype "passive"))
      (node (ref "J5") (pin "5") (pinfunction "RDC_5") (pintype "passive"))
      (node (ref "J5") (pin "9") (pinfunction "LED_G_A_9") (pintype "passive"))
      (node (ref "R21") (pin "2") (pinfunction "2_2") (pintype "passive"))
      (node (ref "R22") (pin "2") (pinfunction "2_2") (pintype "passive"))
      (node (ref "R23") (pin "2") (pinfunction "2_2") (pintype "passive"))
      (node (ref "R24") (pin "2") (pinfunction "2_2") (pintype "passive"))
      (node (ref "R25") (pin "2") (pinfunction "2_2") (pintype "passive"))
      (node (ref "R26") (pin "2") (pinfunction "2_2") (pintype "passive"))
      (node (ref "R27") (pin "2") (pinfunction "2_2") (pintype "passive"))
      (node (ref "TP2") (pin "1") (pinfunction "1_1") (pintype "passive"))
      (node (ref "U4") (pin "5") (pinfunction "VOUT_5") (pintype "power_in"))
      (node (ref "U6") (pin "9") (pinfunction "VDDIO_9") (pintype "power_in"))
      (node (ref "Y2") (pin "4") (pinfunction "VDD_4") (pintype "power_in"))
    )
    (net (code "37") (name "GND") (class "Default")
      (node (ref "C1") (pin "1") (pinfunction "1_1") (pintype "passive"))
      (node (ref "C10") (pin "1") (pinfunction "1_1") (pintype "passive"))
      (node (ref "C11") (pin "1") (pinfunction "1_1") (pintype "passive"))
      (node (ref "C12") (pin "1") (pinfunction "1_1") (pintype "passive"))
      (node (ref "C13") (pin "1") (pinfunction "1_1") (pintype "passive"))
      (node (ref "C14") (pin "1") (pinfunction "1_1") (pintype "passive"))
      (node (ref "C15") (pin "1") (pinfunction "1_1") (pintype "passive"))
      (node (ref "C16") (pin "1") (pinfunction "1_1") (pintype "passive"))
      (node (ref "C17") (pin "1") (pinfunction "1_1") (pintype "passive"))
      (node (ref "C18") (pin "1") (pinfunction "1_1") (pintype "passive"))
      (node (ref "C19") (pin "1") (pinfunction "1_1") (pintype "passive"))
      (node (ref "C2") (pin "1") (pinfunction "1_1") (pintype "passive"))
      (node (ref "C20") (pin "1") (pinfunction "1_1") (pintype "passive"))
      (node (ref "C21") (pin "1") (pinfunction "1_1") (pintype "passive"))
      (node (ref "C22") (pin "1") (pinfunction "1_1") (pintype "passive"))
      (node (ref "C23") (pin "1") (pinfunction "1_1") (pintype "passive"))
      (node (ref "C24") (pin "1") (pinfunction "1_1") (pintype "passive"))
      (node (ref "C28") (pin "2") (pinfunction "2_2") (pintype "passive"))
      (node (ref "C29") (pin "2") (pinfunction "2_2") (pintype "passive"))
      (node (ref "C3") (pin "1") (pinfunction "1_1") (pintype "passive"))
      (node (ref "C30") (pin "1") (pinfunction "1_1") (pintype "passive"))
      (node (ref "C31") (pin "1") (pinfunction "1_1") (pintype "passive"))
      (node (ref "C4") (pin "1") (pinfunction "1_1") (pintype "passive"))
      (node (ref "C5") (pin "1") (pinfunction "1_1") (pintype "passive"))
      (node (ref "C6") (pin "1") (pinfunction "1_1") (pintype "passive"))
      (node (ref "C7") (pin "1") (pinfunction "1_1") (pintype "passive"))
      (node (ref "C8") (pin "1") (pinfunction "1_1") (pintype "passive"))
      (node (ref "C9") (pin "1") (pinfunction "1_1") (pintype "passive"))
      (node (ref "D1") (pin "2") (pinfunction "2_2") (pintype "passive"))
      (node (ref "D4") (pin "1") (pinfunction "1_1") (pintype "passive"))
      (node (ref "D5") (pin "1") (pinfunction "1_1") (pintype "passive"))
      (node (ref "D6") (pin "1") (pinfunction "1_1") (pintype "passive"))
      (node (ref "J1") (pin "2") (pinfunction "2_2") (pintype "passive"))
      (node (ref "J1") (pin "3") (pinfunction "3_3") (pintype "passive"))
      (node (ref "J2") (pin "2") (pinfunction "2_2") (pintype "passive"))
      (node (ref "J3") (pin "5") (pinfunction "GND_5") (pintype "passive"))
      (node (ref "J3") (pin "SH") (pinfunction "SH_SH") (pintype "passive"))
      (node (ref "J4") (pin "1") (pinfunction "1_1") (pintype "passive"))
      (node (ref "J5") (pin "8") (pinfunction "CGND_8") (pintype "passive"))
      (node (ref "R15") (pin "1") (pinfunction "1_1") (pintype "passive"))
      (node (ref "R3") (pin "1") (pinfunction "1_1") (pintype "passive"))
      (node (ref "R33") (pin "1") (pinfunction "1_1") (pintype "passive"))
      (node (ref "RST1") (pin "2") (pintype "passive"))
      (node (ref "U1") (pin "2") (pinfunction "GND_2") (pintype "power_in"))
      (node (ref "U2") (pin "33") (pinfunction "EP_33") (pintype "power_in"))
      (node (ref "U3") (pin "4") (pinfunction "VSS_4") (pintype "power_in"))
      (node (ref "U4") (pin "2") (pinfunction "GND_2") (pintype "power_in"))
      (node (ref "U5") (pin "15") (pinfunction "GND_15") (pintype "power_in"))
      (node (ref "U6") (pin "25") (pinfunction "VSS_25") (pintype "power_in"))
      (node (ref "UART1") (pin "4") (pinfunction "4_4") (pintype "passive"))
      (node (ref "UART1") (pin "MP1") (pinfunction "MP1_MP1") (pintype "passive"))
      (node (ref "UART1") (pin "MP2") (pinfunction "MP2_MP2") (pintype "passive"))
      (node (ref "Y1") (pin "2") (pinfunction "GND_2") (pintype "power_in"))
      (node (ref "Y1") (pin "4") (pinfunction "GND_4") (pintype "power_in"))
      (node (ref "Y2") (pin "2") (pinfunction "GND/Case_2") (pintype "power_in"))
    )
    (net (code "38") (name "Net-(C3-Pad2)") (class "Default")
      (node (ref "C3") (pin "2") (pinfunction "2_2") (pintype "passive"))
      (node (ref "L1") (pin "2") (pinfunction "2_2") (pintype "passive"))
      (node (ref "U2") (pin "2") (pinfunction "VDD3P3_2") (pintype "power_in"))
      (node (ref "U2") (pin "3") (pinfunction "VDD3P3_3") (pintype "power_in"))
    )
    (net (code "39") (name "Net-(C11-Pad2)") (class "Default")
      (node (ref "C11") (pin "2") (pinfunction "2_2") (pintype "passive"))
      (node (ref "J2") (pin "1") (pinfunction "1_1") (pintype "passive"))
      (node (ref "L2") (pin "1") (pinfunction "1_1") (pintype "passive"))
    )
    (net (code "40") (name "Net-(D1-Pad1)") (class "Default")
      (node (ref "D1") (pin "1") (pinfunction "1_1") (pintype "passive"))
      (node (ref "R1") (pin "2") (pinfunction "2_2") (pintype "passive"))
    )
    (net (code "41") (name "Net-(D2-Pad1)") (class "Default")
      (node (ref "D2") (pin "1") (pinfunction "1_1") (pintype "passive"))
      (node (ref "J1") (pin "1") (pinfunction "1_1") (pintype "passive"))
    )
    (net (code "42") (name "Net-(J3-VCC)") (class "Default")
      (node (ref "D3") (pin "1") (pinfunction "1_1") (pintype "passive"))
      (node (ref "J3") (pin "1") (pinfunction "VCC_1") (pintype "passive"))
    )
    (net (code "43") (name "Net-(J5-LED_G_K)") (class "Default")
      (node (ref "J5") (pin "10") (pinfunction "LED_G_K_10") (pintype "passive"))
      (node (ref "R28") (pin "1") (pinfunction "1_1") (pintype "passive"))
    )
    (net (code "44") (name "Net-(J5-LED_Y_K)") (class "Default")
      (node (ref "J5") (pin "11") (pinfunction "LED_Y_K_11") (pintype "passive"))
      (node (ref "R30") (pin "1") (pinfunction "1_1") (pintype "passive"))
    )
    (net (code "45") (name "Net-(R12-Pad2)") (class "Default")
      (node (ref "R12") (pin "2") (pinfunction "2_2") (pintype "passive"))
      (node (ref "RXD1") (pin "1") (pinfunction "1_1") (pintype "passive"))
    )
    (net (code "46") (name "Net-(R13-Pad2)") (class "Default")
      (node (ref "R13") (pin "2") (pinfunction "2_2") (pintype "passive"))
      (node (ref "TXD1") (pin "1") (pinfunction "1_1") (pintype "passive"))
    )
    (net (code "47") (name "Net-(R16-Pad2)") (class "Default")
      (node (ref "R16") (pin "2") (pinfunction "2_2") (pintype "passive"))
      (node (ref "RS1") (pin "1") (pinfunction "1_1") (pintype "passive"))
    )
    (net (code "48") (name "Net-(R17-Pad2)") (class "Default")
      (node (ref "R17") (pin "2") (pinfunction "2_2") (pintype "passive"))
      (node (ref "RS2") (pin "1") (pinfunction "1_1") (pintype "passive"))
    )
    (net (code "49") (name "Net-(U1-STBY)") (class "Default")
      (node (ref "R2") (pin "1") (pinfunction "1_1") (pintype "passive"))
      (node (ref "R3") (pin "2") (pinfunction "2_2") (pintype "passive"))
      (node (ref "U1") (pin "3") (pinfunction "STBY_3") (pintype "input"))
    )
    (net (code "50") (name "Net-(U2-LNA_IN)") (class "Default")
      (node (ref "C12") (pin "2") (pinfunction "2_2") (pintype "passive"))
      (node (ref "L2") (pin "2") (pinfunction "2_2") (pintype "passive"))
      (node (ref "U2") (pin "1") (pinfunction "LNA_IN_1") (pintype "bidirectional"))
    )
    (net (code "51") (name "Net-(U2-SPICLK)") (class "Default")
      (node (ref "R6") (pin "1") (pinfunction "1_1") (pintype "passive"))
      (node (ref "U2") (pin "22") (pinfunction "SPICLK_22") (pintype "bidirectional"))
    )
    (net (code "52") (name "Net-(U2-SPICS0)") (class "Default")
      (node (ref "R7") (pin "1") (pinfunction "1_1") (pintype "passive"))
      (node (ref "U2") (pin "21") (pinfunction "SPICS0_21") (pintype "bidirectional"))
    )
    (net (code "53") (name "Net-(U2-SPID)") (class "Default")
      (node (ref "R4") (pin "1") (pinfunction "1_1") (pintype "passive"))
      (node (ref "U2") (pin "23") (pinfunction "SPID_23") (pintype "bidirectional"))
    )
    (net (code "54") (name "Net-(U2-SPIHD)") (class "Default")
      (node (ref "R8") (pin "1") (pinfunction "1_1") (pintype "passive"))
      (node (ref "U2") (pin "19") (pinfunction "SPIHD_19") (pintype "bidirectional"))
    )
    (net (code "55") (name "Net-(U2-SPIQ)") (class "Default")
      (node (ref "R5") (pin "1") (pinfunction "1_1") (pintype "passive"))
      (node (ref "U2") (pin "24") (pinfunction "SPIQ_24") (pintype "bidirectional"))
    )
    (net (code "56") (name "Net-(U2-SPIWP)") (class "Default")
      (node (ref "R9") (pin "1") (pinfunction "1_1") (pintype "passive"))
      (node (ref "U2") (pin "20") (pinfunction "SPIWP_20") (pintype "bidirectional"))
    )
    (net (code "57") (name "Net-(U2-U0RXD)") (class "Default")
      (node (ref "R10") (pin "1") (pinfunction "1_1") (pintype "passive"))
      (node (ref "U2") (pin "27") (pinfunction "U0RXD_27") (pintype "bidirectional"))
    )
    (net (code "58") (name "Net-(U4-STBY)") (class "Default")
      (node (ref "R11") (pin "1") (pinfunction "1_1") (pintype "passive"))
      (node (ref "R15") (pin "2") (pinfunction "2_2") (pintype "passive"))
      (node (ref "U4") (pin "3") (pinfunction "STBY_3") (pintype "input"))
    )
    (net (code "59") (name "Net-(U5-C1+)") (class "Default")
      (node (ref "C25") (pin "2") (pinfunction "2_2") (pintype "passive"))
      (node (ref "U5") (pin "1") (pinfunction "C1+_1") (pintype "passive"))
    )
    (net (code "60") (name "Net-(U5-C1-)") (class "Default")
      (node (ref "C25") (pin "1") (pinfunction "1_1") (pintype "passive"))
      (node (ref "U5") (pin "3") (pinfunction "C1-_3") (pintype "passive"))
    )
    (net (code "61") (name "Net-(U5-C2+)") (class "Default")
      (node (ref "C26") (pin "1") (pinfunction "1_1") (pintype "passive"))
      (node (ref "U5") (pin "4") (pinfunction "C2+_4") (pintype "passive"))
    )
    (net (code "62") (name "Net-(U5-C2-)") (class "Default")
      (node (ref "C26") (pin "2") (pinfunction "2_2") (pintype "passive"))
      (node (ref "U5") (pin "5") (pinfunction "C2-_5") (pintype "passive"))
    )
    (net (code "63") (name "Net-(U5-R2IN)") (class "Default")
      (node (ref "J4") (pin "2") (pinfunction "2_2") (pintype "passive"))
      (node (ref "U5") (pin "8") (pinfunction "R2IN_8") (pintype "input"))
    )
    (net (code "64") (name "Net-(U5-VS+)") (class "Default")
      (node (ref "C27") (pin "1") (pinfunction "1_1") (pintype "passive"))
      (node (ref "U5") (pin "2") (pinfunction "VS+_2") (pintype "power_in"))
    )
    (net (code "65") (name "Net-(U5-VS-)") (class "Default")
      (node (ref "C29") (pin "1") (pinfunction "1_1") (pintype "passive"))
      (node (ref "U5") (pin "6") (pinfunction "VS-_6") (pintype "power_in"))
    )
    (net (code "66") (name "Net-(U5-~{R2OUT})") (class "Default")
      (node (ref "R29") (pin "2") (pinfunction "2_2") (pintype "passive"))
      (node (ref "U5") (pin "9") (pinfunction "~{R2OUT}_9") (pintype "output"))
    )
    (net (code "67") (name "Net-(U5-~{T2OUT})") (class "Default")
      (node (ref "J4") (pin "3") (pinfunction "3_3") (pintype "passive"))
      (node (ref "U5") (pin "7") (pinfunction "~{T2OUT}_7") (pintype "output"))
    )
    (net (code "68") (name "Net-(U6-CRS_DV{slash}MODE2)") (class "Default")
      (node (ref "R34") (pin "2") (pinfunction "2_2") (pintype "passive"))
      (node (ref "U6") (pin "11") (pinfunction "CRS_DV/MODE2_11") (pintype "bidirectional"))
    )
    (net (code "69") (name "Net-(U6-MDIO)") (class "Default")
      (node (ref "R26") (pin "1") (pinfunction "1_1") (pintype "passive"))
      (node (ref "U6") (pin "12") (pinfunction "MDIO_12") (pintype "bidirectional"))
    )
    (net (code "70") (name "Net-(U6-RBIAS)") (class "Default")
      (node (ref "R33") (pin "2") (pinfunction "2_2") (pintype "passive"))
      (node (ref "U6") (pin "24") (pinfunction "RBIAS_24") (pintype "passive"))
    )
    (net (code "71") (name "Net-(U6-RXD0{slash}MODE0)") (class "Default")
      (node (ref "R31") (pin "2") (pinfunction "2_2") (pintype "passive"))
      (node (ref "U6") (pin "8") (pinfunction "RXD0/MODE0_8") (pintype "bidirectional"))
    )
    (net (code "72") (name "Net-(U6-RXD1{slash}MODE1)") (class "Default")
      (node (ref "R32") (pin "2") (pinfunction "2_2") (pintype "passive"))
      (node (ref "U6") (pin "7") (pinfunction "RXD1/MODE1_7") (pintype "bidirectional"))
    )
    (net (code "73") (name "Net-(U6-RXER{slash}PHYAD0)") (class "Default")
      (node (ref "R25") (pin "1") (pinfunction "1_1") (pintype "passive"))
      (node (ref "U6") (pin "10") (pinfunction "RXER/PHYAD0_10") (pintype "bidirectional"))
    )
    (net (code "74") (name "Net-(U6-VDD1A)") (class "Default")
      (node (ref "C19") (pin "2") (pinfunction "2_2") (pintype "passive"))
      (node (ref "C20") (pin "2") (pinfunction "2_2") (pintype "passive"))
      (node (ref "C21") (pin "2") (pinfunction "2_2") (pintype "passive"))
      (node (ref "FB1") (pin "1") (pinfunction "1_1") (pintype "passive"))
      (node (ref "U6") (pin "1") (pinfunction "VDD2A_1") (pintype "power_in"))
      (node (ref "U6") (pin "19") (pinfunction "VDD1A_19") (pintype "power_in"))
    )
    (net (code "75") (name "Net-(U6-~{RST})") (class "Default")
      (node (ref "C31") (pin "2") (pinfunction "2_2") (pintype "passive"))
      (node (ref "R27") (pin "1") (pinfunction "1_1") (pintype "passive"))
      (node (ref "U6") (pin "15") (pinfunction "~{RST}_15") (pintype "input"))
    )
    (net (code "76") (name "Net-(Y2-Output)") (class "Default")
      (node (ref "R19") (pin "2") (pinfunction "2_2") (pintype "passive"))
      (node (ref "R20") (pin "1") (pinfunction "1_1") (pintype "passive"))
      (node (ref "Y2") (pin "3") (pinfunction "Output_3") (pintype "output"))
    )
    (net (code "77") (name "VDD_3V3") (class "Default")
      (node (ref "C1") (pin "2") (pinfunction "2_2") (pintype "passive"))
      (node (ref "C10") (pin "2") (pinfunction "2_2") (pintype "passive"))
      (node (ref "C2") (pin "2") (pinfunction "2_2") (pintype "passive"))
      (node (ref "C27") (pin "2") (pinfunction "2_2") (pintype "passive"))
      (node (ref "C28") (pin "1") (pinfunction "1_1") (pintype "passive"))
      (node (ref "C4") (pin "2") (pinfunction "2_2") (pintype "passive"))
      (node (ref "C5") (pin "2") (pinfunction "2_2") (pintype "passive"))
      (node (ref "C6") (pin "2") (pinfunction "2_2") (pintype "passive"))
      (node (ref "C7") (pin "2") (pinfunction "2_2") (pintype "passive"))
      (node (ref "C8") (pin "2") (pinfunction "2_2") (pintype "passive"))
      (node (ref "J4") (pin "5") (pinfunction "5_5") (pintype "passive"))
      (node (ref "L1") (pin "1") (pinfunction "1_1") (pintype "passive"))
      (node (ref "R12") (pin "1") (pinfunction "1_1") (pintype "passive"))
      (node (ref "R13") (pin "1") (pinfunction "1_1") (pintype "passive"))
      (node (ref "R14") (pin "2") (pinfunction "2_2") (pintype "passive"))
      (node (ref "R16") (pin "1") (pinfunction "1_1") (pintype "passive"))
      (node (ref "R17") (pin "1") (pinfunction "1_1") (pintype "passive"))
      (node (ref "TP1") (pin "1") (pinfunction "1_1") (pintype "passive"))
      (node (ref "U1") (pin "5") (pinfunction "VOUT_5") (pintype "power_in"))
      (node (ref "U2") (pin "11") (pinfunction "VDD3P3_RTC_11") (pintype "power_in"))
      (node (ref "U2") (pin "17") (pinfunction "VDD3P3_CPU_17") (pintype "power_in"))
      (node (ref "U2") (pin "31") (pinfunction "VDDA_31") (pintype "power_in"))
      (node (ref "U2") (pin "32") (pinfunction "VDDA_32") (pintype "power_in"))
      (node (ref "U5") (pin "16") (pinfunction "VCC_16") (pintype "power_in"))
      (node (ref "UART1") (pin "1") (pinfunction "1_1") (pintype "passive"))
    )
    (net (code "78") (name "unconnected-(J3-ID-Pad4)") (class "Default")
      (node (ref "J3") (pin "4") (pinfunction "ID_4") (pintype "passive+no_connect"))
    )
    (net (code "79") (name "unconnected-(J4-MH1-Pad10)") (class "Default")
      (node (ref "J4") (pin "10") (pinfunction "MH1_10") (pintype "passive"))
    )
    (net (code "80") (name "unconnected-(J4-MH2-Pad11)") (class "Default")
      (node (ref "J4") (pin "11") (pinfunction "MH2_11") (pintype "passive"))
    )
    (net (code "81") (name "unconnected-(J4-Pad4)") (class "Default")
      (node (ref "J4") (pin "4") (pinfunction "4_4") (pintype "passive"))
    )
    (net (code "82") (name "unconnected-(J4-Pad6)") (class "Default")
      (node (ref "J4") (pin "6") (pinfunction "6_6") (pintype "passive"))
    )
    (net (code "83") (name "unconnected-(J4-Pad7)") (class "Default")
      (node (ref "J4") (pin "7") (pinfunction "7_7") (pintype "passive"))
    )
    (net (code "84") (name "unconnected-(J4-Pad8)") (class "Default")
      (node (ref "J4") (pin "8") (pinfunction "8_8") (pintype "passive"))
    )
    (net (code "85") (name "unconnected-(J4-Pad9)") (class "Default")
      (node (ref "J4") (pin "9") (pinfunction "9_9") (pintype "passive"))
    )
    (net (code "86") (name "unconnected-(J5-NC-Pad7)") (class "Default")
      (node (ref "J5") (pin "7") (pinfunction "NC_7") (pintype "passive"))
    )
    (net (code "87") (name "unconnected-(U1-NC-Pad4)") (class "Default")
      (node (ref "U1") (pin "4") (pinfunction "NC_4") (pintype "passive"))
    )
    (net (code "88") (name "unconnected-(U2-XTAL_32K_N-Pad5)") (class "Default")
      (node (ref "U2") (pin "5") (pinfunction "XTAL_32K_N_5") (pintype "bidirectional+no_connect"))
    )
    (net (code "89") (name "unconnected-(U2-XTAL_32K_P-Pad4)") (class "Default")
      (node (ref "U2") (pin "4") (pinfunction "XTAL_32K_P_4") (pintype "bidirectional+no_connect"))
    )
    (net (code "90") (name "unconnected-(U4-NC-Pad4)") (class "Default")
      (node (ref "U4") (pin "4") (pinfunction "NC_4") (pintype "passive"))
    )
    (net (code "91") (name "unconnected-(U5-R1IN-Pad13)") (class "Default")
      (node (ref "U5") (pin "13") (pinfunction "R1IN_13") (pintype "input+no_connect"))
    )
    (net (code "92") (name "unconnected-(U5-T1IN-Pad11)") (class "Default")
      (node (ref "U5") (pin "11") (pinfunction "T1IN_11") (pintype "input+no_connect"))
    )
    (net (code "93") (name "unconnected-(U5-~{R1OUT}-Pad12)") (class "Default")
      (node (ref "U5") (pin "12") (pinfunction "~{R1OUT}_12") (pintype "output+no_connect"))
    )
    (net (code "94") (name "unconnected-(U5-~{T1OUT}-Pad14)") (class "Default")
      (node (ref "U5") (pin "14") (pinfunction "~{T1OUT}_14") (pintype "output+no_connect"))
    )
    (net (code "95") (name "unconnected-(U6-XTAL2-Pad4)") (class "Default")
      (node (ref "U6") (pin "4") (pinfunction "XTAL2_4") (pintype "input+no_connect"))
    )
    (net (code "96") (name "unconnected-(Y2-~{STBY}-Pad1)") (class "Default")
      (node (ref "Y2") (pin "1") (pinfunction "~{STBY}_1") (pintype "input+no_connect"))
    )
  )
)
